# type-1_4_button_v4.net
KiCad netlist of a schematic drawn in EAGLE
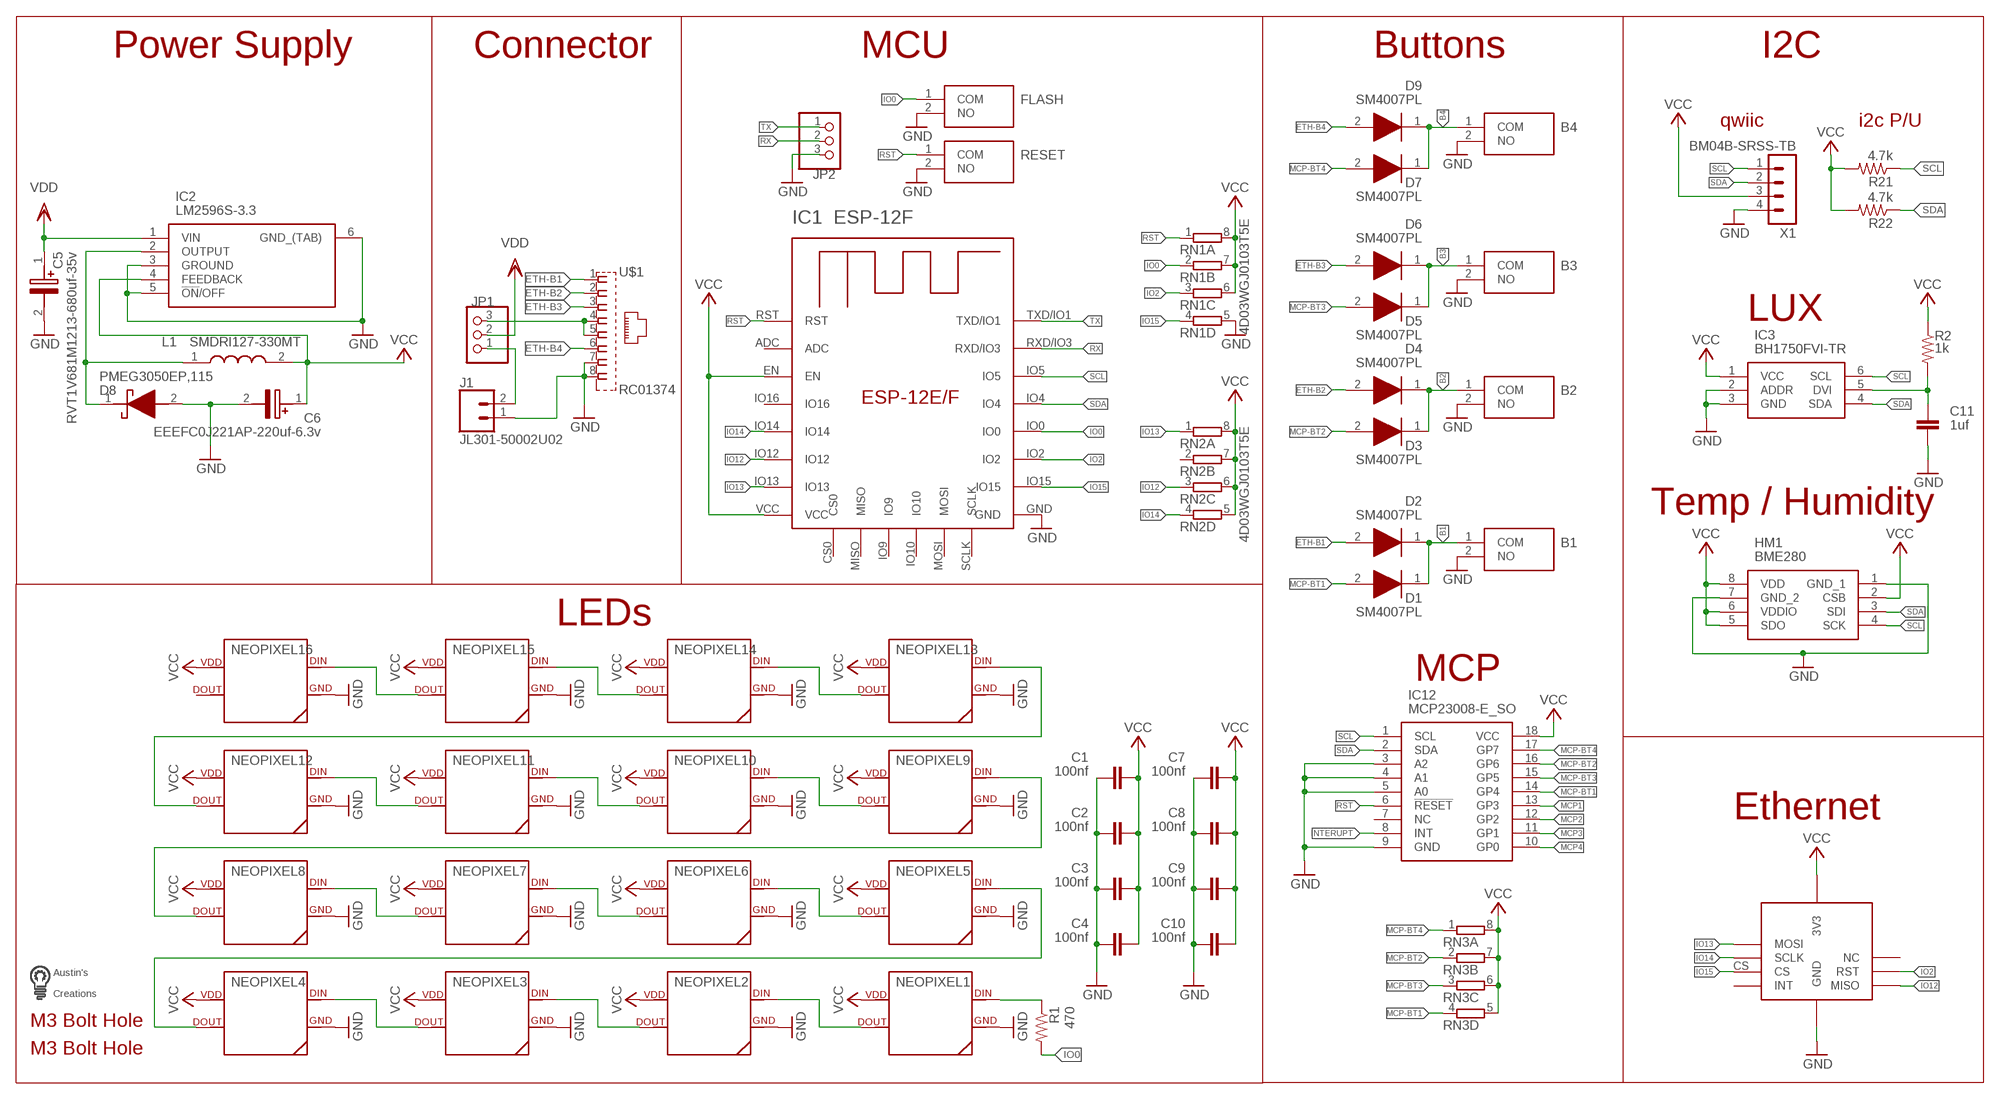
[diagram p0: schematic, sheet 1]

(export (version "E")
  (design (tool "Eeschema 10.0.6"))
  (components
    (comp (ref "B1")
      (value "PTS636_SM25F_SMTR_LFS")
      (footprint "eagle-import:PTS636SM25FSMTRLFS")
      (fields
        (field (name "ARROW_PART_NUMBER") "PTS636 SM25F SMTR LFS")
        (field (name "MOUSER_PART_NUMBER") "611-PTS636SM25FSMTRL")
      )
      (libsource (lib "eagle-import") (part "PTS636_SM25F_SMTR_LFS"))
    )
    (comp (ref "B2")
      (value "PTS636_SM25F_SMTR_LFS")
      (footprint "eagle-import:PTS636SM25FSMTRLFS")
      (fields
        (field (name "ARROW_PART_NUMBER") "PTS636 SM25F SMTR LFS")
        (field (name "MOUSER_PART_NUMBER") "611-PTS636SM25FSMTRL")
      )
      (libsource (lib "eagle-import") (part "PTS636_SM25F_SMTR_LFS"))
    )
    (comp (ref "B3")
      (value "PTS636_SM25F_SMTR_LFS")
      (footprint "eagle-import:PTS636SM25FSMTRLFS")
      (fields
        (field (name "ARROW_PART_NUMBER") "PTS636 SM25F SMTR LFS")
        (field (name "MOUSER_PART_NUMBER") "611-PTS636SM25FSMTRL")
      )
      (libsource (lib "eagle-import") (part "PTS636_SM25F_SMTR_LFS"))
    )
    (comp (ref "B4")
      (value "PTS636_SM25F_SMTR_LFS")
      (footprint "eagle-import:PTS636SM25FSMTRLFS")
      (fields
        (field (name "ARROW_PART_NUMBER") "PTS636 SM25F SMTR LFS")
        (field (name "MOUSER_PART_NUMBER") "611-PTS636SM25FSMTRL")
      )
      (libsource (lib "eagle-import") (part "PTS636_SM25F_SMTR_LFS"))
    )
    (comp (ref "C1")
      (value "100nf")
      (footprint "eagle-import:C0603")
      (libsource (lib "eagle-import") (part "C-EUC0603"))
    )
    (comp (ref "C2")
      (value "100nf")
      (footprint "eagle-import:C0603")
      (libsource (lib "eagle-import") (part "C-EUC0603"))
    )
    (comp (ref "C3")
      (value "100nf")
      (footprint "eagle-import:C0603")
      (libsource (lib "eagle-import") (part "C-EUC0603"))
    )
    (comp (ref "C4")
      (value "100nf")
      (footprint "eagle-import:C0603")
      (libsource (lib "eagle-import") (part "C-EUC0603"))
    )
    (comp (ref "C5")
      (value "RVT1V681M1213-680uf-35v")
      (footprint "eagle-import:CAPAE1350X1400N")
      (fields
        (field (name "MANUFACTURER_PART_NUMBER") "EEE-HD1V681AQ")
        (field (name "MOUSER_PART_NUMBER") "667-EEE-HD1V681AQ")
      )
      (libsource (lib "eagle-import") (part "EEE-HD1V681AQ"))
    )
    (comp (ref "C6")
      (value "EEEFC0J221AP-220uf-6.3v")
      (footprint "eagle-import:CAPAE830X650N")
      (fields (field (name "MANUFACTURER_PART_NUMBER") "EEEFC0J221AP"))
      (libsource (lib "eagle-import") (part "EEEFC0J221AP"))
    )
    (comp (ref "C7")
      (value "100nf")
      (footprint "eagle-import:C0603")
      (libsource (lib "eagle-import") (part "C-EUC0603"))
    )
    (comp (ref "C8")
      (value "100nf")
      (footprint "eagle-import:C0603")
      (libsource (lib "eagle-import") (part "C-EUC0603"))
    )
    (comp (ref "C9")
      (value "100nf")
      (footprint "eagle-import:C0603")
      (libsource (lib "eagle-import") (part "C-EUC0603"))
    )
    (comp (ref "C10")
      (value "100nf")
      (footprint "eagle-import:C0603")
      (libsource (lib "eagle-import") (part "C-EUC0603"))
    )
    (comp (ref "C11")
      (value "1uf")
      (footprint "eagle-import:C0603")
      (libsource (lib "eagle-import") (part "C-EUC0603"))
    )
    (comp (ref "D1")
      (value "SM4007PL")
      (footprint "eagle-import:SODFL3718X125N")
      (libsource (lib "eagle-import") (part "SM4007PL"))
    )
    (comp (ref "D2")
      (value "SM4007PL")
      (footprint "eagle-import:SODFL3718X125N")
      (libsource (lib "eagle-import") (part "SM4007PL"))
    )
    (comp (ref "D3")
      (value "SM4007PL")
      (footprint "eagle-import:SODFL3718X125N")
      (libsource (lib "eagle-import") (part "SM4007PL"))
    )
    (comp (ref "D4")
      (value "SM4007PL")
      (footprint "eagle-import:SODFL3718X125N")
      (libsource (lib "eagle-import") (part "SM4007PL"))
    )
    (comp (ref "D5")
      (value "SM4007PL")
      (footprint "eagle-import:SODFL3718X125N")
      (libsource (lib "eagle-import") (part "SM4007PL"))
    )
    (comp (ref "D6")
      (value "SM4007PL")
      (footprint "eagle-import:SODFL3718X125N")
      (libsource (lib "eagle-import") (part "SM4007PL"))
    )
    (comp (ref "D7")
      (value "SM4007PL")
      (footprint "eagle-import:SODFL3718X125N")
      (libsource (lib "eagle-import") (part "SM4007PL"))
    )
    (comp (ref "D8")
      (value "PMEG3050EP,115")
      (footprint "eagle-import:PMEG3050EP115")
      (fields (field (name "MOUSER_PART_NUMBER") "771-PMEG3050EP115"))
      (libsource (lib "eagle-import") (part "PMEG3050EP,115"))
    )
    (comp (ref "D9")
      (value "SM4007PL")
      (footprint "eagle-import:SODFL3718X125N")
      (libsource (lib "eagle-import") (part "SM4007PL"))
    )
    (comp (ref "FLASH")
      (value "PTS636_SM25F_SMTR_LFS")
      (footprint "eagle-import:PTS636SM25FSMTRLFS")
      (fields
        (field (name "ARROW_PART_NUMBER") "PTS636 SM25F SMTR LFS")
        (field (name "MOUSER_PART_NUMBER") "611-PTS636SM25FSMTRL")
      )
      (libsource (lib "eagle-import") (part "PTS636_SM25F_SMTR_LFS"))
    )
    (comp (ref "HM1")
      (value "BME280")
      (footprint "eagle-import:BME280")
      (fields (field (name "MOUSER_PART_NUMBER") "262-BME280"))
      (libsource (lib "eagle-import") (part "BME280"))
    )
    (comp (ref "IC1")
      (value "ESP-12F")
      (footprint "eagle-import:ESP-12E")
      (libsource (lib "eagle-import") (part "ESP-12E/F"))
    )
    (comp (ref "IC2")
      (value "LM2596S-3.3")
      (footprint "eagle-import:TO170P1435X465-6N")
      (fields
        (field (name "MANUFACTURER_PART_NUMBER") "LM2596S-3.3/NOPB")
        (field (name "MOUSER_PART_NUMBER") "926-LM2596S-3.3/NOPB")
      )
      (libsource (lib "eagle-import") (part "LM2596S-3.3_NOPB"))
    )
    (comp (ref "IC3")
      (value "BH1750FVI-TR")
      (footprint "eagle-import:WSOF6")
      (fields (field (name "MOUSER_PART_NUMBER") "755-BH1750FVI-TR"))
      (libsource (lib "eagle-import") (part "BH1750FVI-TR"))
    )
    (comp (ref "IC12")
      (value "MCP23008-E_SO")
      (footprint "eagle-import:SOIC127P1030X265-18N")
      (fields
        (field (name "ARROW_PART_NUMBER") "MCP23008-E/SO")
        (field (name "MOUSER_PART_NUMBER") "579-MCP23008-E/SO")
      )
      (libsource (lib "eagle-import") (part "MCP23008-E_SO"))
    )
    (comp (ref "J1")
      (value "JL301-50002U02")
      (footprint "eagle-import:SCREWTERMINAL-5MM-2")
      (libsource (lib "eagle-import") (part "2PINBLOCK"))
    )
    (comp (ref "JP1")
      (value "PINHD-1X3")
      (footprint "eagle-import:1X03")
      (libsource (lib "eagle-import") (part "PINHD-1X3"))
    )
    (comp (ref "JP2")
      (value "PINHD-1X3")
      (footprint "eagle-import:1X03")
      (libsource (lib "eagle-import") (part "PINHD-1X3"))
    )
    (comp (ref "L1")
      (value "SMDRI127-330MT")
      (footprint "eagle-import:INDPM120120X800N")
      (fields
        (field (name "MANUFACTURER_PART_NUMBER") "CDRH127/LDNP-330MC")
        (field (name "MOUSER_PART_NUMBER") "851-CDRH127LDNP330MC")
      )
      (libsource (lib "eagle-import") (part "CDRH127_LDNP-330MC"))
    )
    (comp (ref "NEOPIXEL1")
      (value "SK6812NEOPIXEL5050")
      (footprint "eagle-import:SK6812")
      (libsource (lib "eagle-import") (part "SK68125050NEOPIXEL"))
    )
    (comp (ref "NEOPIXEL2")
      (value "SK6812NEOPIXEL5050")
      (footprint "eagle-import:SK6812")
      (libsource (lib "eagle-import") (part "SK68125050NEOPIXEL"))
    )
    (comp (ref "NEOPIXEL3")
      (value "SK6812NEOPIXEL5050")
      (footprint "eagle-import:SK6812")
      (libsource (lib "eagle-import") (part "SK68125050NEOPIXEL"))
    )
    (comp (ref "NEOPIXEL4")
      (value "SK6812NEOPIXEL5050")
      (footprint "eagle-import:SK6812")
      (libsource (lib "eagle-import") (part "SK68125050NEOPIXEL"))
    )
    (comp (ref "NEOPIXEL5")
      (value "SK6812NEOPIXEL5050")
      (footprint "eagle-import:SK6812")
      (libsource (lib "eagle-import") (part "SK68125050NEOPIXEL"))
    )
    (comp (ref "NEOPIXEL6")
      (value "SK6812NEOPIXEL5050")
      (footprint "eagle-import:SK6812")
      (libsource (lib "eagle-import") (part "SK68125050NEOPIXEL"))
    )
    (comp (ref "NEOPIXEL7")
      (value "SK6812NEOPIXEL5050")
      (footprint "eagle-import:SK6812")
      (libsource (lib "eagle-import") (part "SK68125050NEOPIXEL"))
    )
    (comp (ref "NEOPIXEL8")
      (value "SK6812NEOPIXEL5050")
      (footprint "eagle-import:SK6812")
      (libsource (lib "eagle-import") (part "SK68125050NEOPIXEL"))
    )
    (comp (ref "NEOPIXEL9")
      (value "SK6812NEOPIXEL5050")
      (footprint "eagle-import:SK6812")
      (libsource (lib "eagle-import") (part "SK68125050NEOPIXEL"))
    )
    (comp (ref "NEOPIXEL10")
      (value "SK6812NEOPIXEL5050")
      (footprint "eagle-import:SK6812")
      (libsource (lib "eagle-import") (part "SK68125050NEOPIXEL"))
    )
    (comp (ref "NEOPIXEL11")
      (value "SK6812NEOPIXEL5050")
      (footprint "eagle-import:SK6812")
      (libsource (lib "eagle-import") (part "SK68125050NEOPIXEL"))
    )
    (comp (ref "NEOPIXEL12")
      (value "SK6812NEOPIXEL5050")
      (footprint "eagle-import:SK6812")
      (libsource (lib "eagle-import") (part "SK68125050NEOPIXEL"))
    )
    (comp (ref "NEOPIXEL13")
      (value "SK6812NEOPIXEL5050")
      (footprint "eagle-import:SK6812")
      (libsource (lib "eagle-import") (part "SK68125050NEOPIXEL"))
    )
    (comp (ref "NEOPIXEL14")
      (value "SK6812NEOPIXEL5050")
      (footprint "eagle-import:SK6812")
      (libsource (lib "eagle-import") (part "SK68125050NEOPIXEL"))
    )
    (comp (ref "NEOPIXEL15")
      (value "SK6812NEOPIXEL5050")
      (footprint "eagle-import:SK6812")
      (libsource (lib "eagle-import") (part "SK68125050NEOPIXEL"))
    )
    (comp (ref "NEOPIXEL16")
      (value "SK6812NEOPIXEL5050")
      (footprint "eagle-import:SK6812")
      (libsource (lib "eagle-import") (part "SK68125050NEOPIXEL"))
    )
    (comp (ref "R1")
      (value "470")
      (footprint "eagle-import:R0603")
      (libsource (lib "eagle-import") (part "resistor_348_R-US_R0603"))
    )
    (comp (ref "R2")
      (value "1k")
      (footprint "eagle-import:R0603")
      (libsource (lib "eagle-import") (part "resistor_348_R-US_R0603"))
    )
    (comp (ref "R21")
      (value "4.7k")
      (footprint "eagle-import:R0603")
      (libsource (lib "eagle-import") (part "R-US_R0603"))
    )
    (comp (ref "R22")
      (value "4.7k")
      (footprint "eagle-import:R0603")
      (libsource (lib "eagle-import") (part "R-US_R0603"))
    )
    (comp (ref "RESET")
      (value "PTS636_SM25F_SMTR_LFS")
      (footprint "eagle-import:PTS636SM25FSMTRLFS")
      (fields
        (field (name "ARROW_PART_NUMBER") "PTS636 SM25F SMTR LFS")
        (field (name "MOUSER_PART_NUMBER") "611-PTS636SM25FSMTRL")
      )
      (libsource (lib "eagle-import") (part "PTS636_SM25F_SMTR_LFS"))
    )
    (comp (ref "RN1")
      (value "4R-N0603-ARC")
      (footprint "eagle-import:0603-ARC")
      (libsource (lib "eagle-import") (part "4R-N0603-ARC"))
    )
    (comp (ref "RN2")
      (value "4R-N0603-ARC")
      (footprint "eagle-import:0603-ARC")
      (libsource (lib "eagle-import") (part "4R-N0603-ARC"))
    )
    (comp (ref "RN3")
      (value "4R-N0603-ARC")
      (footprint "eagle-import:0603-ARC")
      (libsource (lib "eagle-import") (part "4R-N0603-ARC"))
    )
    (comp (ref "U$1")
      (value "RC01374")
      (footprint "eagle-import:RC01374")
      (libsource (lib "eagle-import") (part "RC01374"))
    )
    (comp (ref "U$3")
      (value "W5500MODULE")
      (footprint "eagle-import:W5500MODULE")
      (libsource (lib "eagle-import") (part "W5500MODULE"))
    )
    (comp (ref "U$4")
      (value "M3BOLTHOLE")
      (footprint "eagle-import:M3BOLTHOLE")
      (libsource (lib "eagle-import") (part "M3BOLTHOLE"))
    )
    (comp (ref "U$5")
      (value "M3BOLTHOLE")
      (footprint "eagle-import:M3BOLTHOLE")
      (libsource (lib "eagle-import") (part "M3BOLTHOLE"))
    )
    (comp (ref "U$6")
      (value "LOGOMED")
      (footprint "eagle-import:LOGOMED")
      (libsource (lib "eagle-import") (part "LOGOMED"))
    )
    (comp (ref "X1")
      (value "BM04B-SRSS-TB")
      (footprint "eagle-import:BM04B-SRSS-TB")
      (libsource (lib "eagle-import") (part "BM04B-SRSS-TB"))
    )
  )
  (nets
    (net (code "1") (name "B1") (class "Default")
      (node (ref "B1") (pin "1") (pinfunction "COM_1") (pintype "bidirectional"))
      (node (ref "D1") (pin "1") (pinfunction "K_1") (pintype "bidirectional"))
      (node (ref "D2") (pin "1") (pinfunction "K_1") (pintype "bidirectional"))
    )
    (net (code "2") (name "B2") (class "Default")
      (node (ref "B2") (pin "1") (pinfunction "COM_1") (pintype "bidirectional"))
      (node (ref "D3") (pin "1") (pinfunction "K_1") (pintype "bidirectional"))
      (node (ref "D4") (pin "1") (pinfunction "K_1") (pintype "bidirectional"))
    )
    (net (code "3") (name "B3") (class "Default")
      (node (ref "B3") (pin "1") (pinfunction "COM_1") (pintype "bidirectional"))
      (node (ref "D5") (pin "1") (pinfunction "K_1") (pintype "bidirectional"))
      (node (ref "D6") (pin "1") (pinfunction "K_1") (pintype "bidirectional"))
    )
    (net (code "4") (name "B4") (class "Default")
      (node (ref "B4") (pin "1") (pinfunction "COM_1") (pintype "bidirectional"))
      (node (ref "D7") (pin "1") (pinfunction "K_1") (pintype "bidirectional"))
      (node (ref "D9") (pin "1") (pinfunction "K_1") (pintype "bidirectional"))
    )
    (net (code "5") (name "ETH-B1") (class "Default")
      (node (ref "D2") (pin "2") (pinfunction "A_2") (pintype "bidirectional"))
      (node (ref "U$1") (pin "1") (pinfunction "1_1") (pintype "passive"))
    )
    (net (code "6") (name "ETH-B2") (class "Default")
      (node (ref "D4") (pin "2") (pinfunction "A_2") (pintype "bidirectional"))
      (node (ref "U$1") (pin "2") (pinfunction "2_2") (pintype "passive"))
    )
    (net (code "7") (name "ETH-B3") (class "Default")
      (node (ref "D6") (pin "2") (pinfunction "A_2") (pintype "bidirectional"))
      (node (ref "U$1") (pin "3") (pinfunction "3_3") (pintype "passive"))
    )
    (net (code "8") (name "ETH-B4") (class "Default")
      (node (ref "D9") (pin "2") (pinfunction "A_2") (pintype "bidirectional"))
      (node (ref "U$1") (pin "6") (pinfunction "6_6") (pintype "passive"))
    )
    (net (code "9") (name "GND") (class "Default")
      (node (ref "B1") (pin "2") (pinfunction "NO_2") (pintype "bidirectional"))
      (node (ref "B2") (pin "2") (pinfunction "NO_2") (pintype "bidirectional"))
      (node (ref "B3") (pin "2") (pinfunction "NO_2") (pintype "bidirectional"))
      (node (ref "B4") (pin "2") (pinfunction "NO_2") (pintype "bidirectional"))
      (node (ref "C1") (pin "1") (pinfunction "1_1") (pintype "passive"))
      (node (ref "C10") (pin "1") (pinfunction "1_1") (pintype "passive"))
      (node (ref "C11") (pin "2") (pinfunction "2_2") (pintype "passive"))
      (node (ref "C2") (pin "1") (pinfunction "1_1") (pintype "passive"))
      (node (ref "C3") (pin "1") (pinfunction "1_1") (pintype "passive"))
      (node (ref "C4") (pin "1") (pinfunction "1_1") (pintype "passive"))
      (node (ref "C5") (pin "2") (pinfunction "-_2") (pintype "bidirectional"))
      (node (ref "C6") (pin "2") (pinfunction "-_2") (pintype "bidirectional"))
      (node (ref "C7") (pin "1") (pinfunction "1_1") (pintype "passive"))
      (node (ref "C8") (pin "1") (pinfunction "1_1") (pintype "passive"))
      (node (ref "C9") (pin "1") (pinfunction "1_1") (pintype "passive"))
      (node (ref "D8") (pin "2") (pinfunction "A_2") (pintype "bidirectional"))
      (node (ref "FLASH") (pin "2") (pinfunction "NO_2") (pintype "bidirectional"))
      (node (ref "HM1") (pin "1") (pinfunction "GND_1_1") (pintype "power_in"))
      (node (ref "HM1") (pin "7") (pinfunction "GND_2_7") (pintype "power_in"))
      (node (ref "IC1") (pin "GND") (pinfunction "GND_GND") (pintype "power_in"))
      (node (ref "IC12") (pin "3") (pinfunction "A2_3") (pintype "bidirectional"))
      (node (ref "IC12") (pin "4") (pinfunction "A1_4") (pintype "bidirectional"))
      (node (ref "IC12") (pin "5") (pinfunction "A0_5") (pintype "bidirectional"))
      (node (ref "IC12") (pin "9") (pinfunction "GND_9") (pintype "bidirectional"))
      (node (ref "IC2") (pin "3") (pinfunction "GROUND_3") (pintype "bidirectional"))
      (node (ref "IC2") (pin "5") (pinfunction "~{ON}/OFF_5") (pintype "bidirectional"))
      (node (ref "IC2") (pin "6") (pinfunction "GND_(TAB)_6") (pintype "power_in"))
      (node (ref "IC3") (pin "2") (pinfunction "ADDR_2") (pintype "bidirectional"))
      (node (ref "IC3") (pin "3") (pinfunction "GND_3") (pintype "bidirectional"))
      (node (ref "J1") (pin "1") (pinfunction "1_1") (pintype "passive"))
      (node (ref "JP2") (pin "3") (pinfunction "3_3") (pintype "passive"))
      (node (ref "NEOPIXEL1") (pin "3") (pinfunction "GND_3") (pintype "bidirectional"))
      (node (ref "NEOPIXEL10") (pin "3") (pinfunction "GND_3") (pintype "bidirectional"))
      (node (ref "NEOPIXEL11") (pin "3") (pinfunction "GND_3") (pintype "bidirectional"))
      (node (ref "NEOPIXEL12") (pin "3") (pinfunction "GND_3") (pintype "bidirectional"))
      (node (ref "NEOPIXEL13") (pin "3") (pinfunction "GND_3") (pintype "bidirectional"))
      (node (ref "NEOPIXEL14") (pin "3") (pinfunction "GND_3") (pintype "bidirectional"))
      (node (ref "NEOPIXEL15") (pin "3") (pinfunction "GND_3") (pintype "bidirectional"))
      (node (ref "NEOPIXEL16") (pin "3") (pinfunction "GND_3") (pintype "bidirectional"))
      (node (ref "NEOPIXEL2") (pin "3") (pinfunction "GND_3") (pintype "bidirectional"))
      (node (ref "NEOPIXEL3") (pin "3") (pinfunction "GND_3") (pintype "bidirectional"))
      (node (ref "NEOPIXEL4") (pin "3") (pinfunction "GND_3") (pintype "bidirectional"))
      (node (ref "NEOPIXEL5") (pin "3") (pinfunction "GND_3") (pintype "bidirectional"))
      (node (ref "NEOPIXEL6") (pin "3") (pinfunction "GND_3") (pintype "bidirectional"))
      (node (ref "NEOPIXEL7") (pin "3") (pinfunction "GND_3") (pintype "bidirectional"))
      (node (ref "NEOPIXEL8") (pin "3") (pinfunction "GND_3") (pintype "bidirectional"))
      (node (ref "NEOPIXEL9") (pin "3") (pinfunction "GND_3") (pintype "bidirectional"))
      (node (ref "RESET") (pin "2") (pinfunction "NO_2") (pintype "bidirectional"))
      (node (ref "RN1") (pin "5") (pinfunction "2_5") (pintype "passive"))
      (node (ref "U$1") (pin "7") (pinfunction "7_7") (pintype "passive"))
      (node (ref "U$1") (pin "8") (pinfunction "8_8") (pintype "passive"))
      (node (ref "U$3") (pin "GND1") (pinfunction "GND_GND1") (pintype "bidirectional"))
      (node (ref "U$3") (pin "GND2") (pinfunction "GND_GND2") (pintype "bidirectional"))
      (node (ref "U$3") (pin "GND3") (pinfunction "GND_GND3") (pintype "bidirectional"))
      (node (ref "X1") (pin "4") (pinfunction "4_4") (pintype "passive"))
    )
    (net (code "10") (name "INTERUPT") (class "Default")
      (node (ref "IC12") (pin "8") (pinfunction "INT_8") (pintype "bidirectional"))
    )
    (net (code "11") (name "IO0") (class "Default")
      (node (ref "FLASH") (pin "1") (pinfunction "COM_1") (pintype "bidirectional"))
      (node (ref "IC1") (pin "IO0") (pinfunction "IO0_IO0") (pintype "bidirectional"))
      (node (ref "R1") (pin "2") (pinfunction "2_2") (pintype "passive"))
      (node (ref "RN1") (pin "2") (pinfunction "1_2") (pintype "passive"))
    )
    (net (code "12") (name "IO2") (class "Default")
      (node (ref "IC1") (pin "IO2") (pinfunction "IO2_IO2") (pintype "bidirectional"))
      (node (ref "RN1") (pin "3") (pinfunction "1_3") (pintype "passive"))
      (node (ref "U$3") (pin "RST") (pinfunction "RST_RST") (pintype "bidirectional"))
    )
    (net (code "13") (name "IO12") (class "Default")
      (node (ref "IC1") (pin "IO12") (pinfunction "IO12_IO12") (pintype "bidirectional"))
      (node (ref "RN2") (pin "3") (pinfunction "1_3") (pintype "passive"))
      (node (ref "U$3") (pin "MISO") (pinfunction "MISO_MISO") (pintype "bidirectional"))
    )
    (net (code "14") (name "IO13") (class "Default")
      (node (ref "IC1") (pin "IO13") (pinfunction "IO13_IO13") (pintype "bidirectional"))
      (node (ref "RN2") (pin "1") (pinfunction "1_1") (pintype "passive"))
      (node (ref "U$3") (pin "MOSI") (pinfunction "MOSI_MOSI") (pintype "bidirectional"))
    )
    (net (code "15") (name "IO14") (class "Default")
      (node (ref "IC1") (pin "IO14") (pinfunction "IO14_IO14") (pintype "bidirectional"))
      (node (ref "RN2") (pin "4") (pinfunction "1_4") (pintype "passive"))
      (node (ref "U$3") (pin "SCLK") (pinfunction "SCLK_SCLK") (pintype "bidirectional"))
    )
    (net (code "16") (name "IO15") (class "Default")
      (node (ref "IC1") (pin "IO15") (pinfunction "IO15_IO15") (pintype "bidirectional"))
      (node (ref "RN1") (pin "4") (pinfunction "1_4") (pintype "passive"))
      (node (ref "U$3") (pin "CS") (pinfunction "CS_CS") (pintype "bidirectional"))
    )
    (net (code "17") (name "MCP-BT1") (class "Default")
      (node (ref "D1") (pin "2") (pinfunction "A_2") (pintype "bidirectional"))
      (node (ref "IC12") (pin "14") (pinfunction "GP4_14") (pintype "bidirectional"))
      (node (ref "RN3") (pin "4") (pinfunction "1_4") (pintype "passive"))
    )
    (net (code "18") (name "MCP-BT2") (class "Default")
      (node (ref "D3") (pin "2") (pinfunction "A_2") (pintype "bidirectional"))
      (node (ref "IC12") (pin "16") (pinfunction "GP6_16") (pintype "bidirectional"))
      (node (ref "RN3") (pin "2") (pinfunction "1_2") (pintype "passive"))
    )
    (net (code "19") (name "MCP-BT3") (class "Default")
      (node (ref "D5") (pin "2") (pinfunction "A_2") (pintype "bidirectional"))
      (node (ref "IC12") (pin "15") (pinfunction "GP5_15") (pintype "bidirectional"))
      (node (ref "RN3") (pin "3") (pinfunction "1_3") (pintype "passive"))
    )
    (net (code "20") (name "MCP-BT4") (class "Default")
      (node (ref "D7") (pin "2") (pinfunction "A_2") (pintype "bidirectional"))
      (node (ref "IC12") (pin "17") (pinfunction "GP7_17") (pintype "bidirectional"))
      (node (ref "RN3") (pin "1") (pinfunction "1_1") (pintype "passive"))
    )
    (net (code "21") (name "MCP1") (class "Default")
      (node (ref "IC12") (pin "13") (pinfunction "GP3_13") (pintype "bidirectional"))
    )
    (net (code "22") (name "MCP2") (class "Default")
      (node (ref "IC12") (pin "12") (pinfunction "GP2_12") (pintype "bidirectional"))
    )
    (net (code "23") (name "MCP3") (class "Default")
      (node (ref "IC12") (pin "11") (pinfunction "GP1_11") (pintype "bidirectional"))
    )
    (net (code "24") (name "MCP4") (class "Default")
      (node (ref "IC12") (pin "10") (pinfunction "GP0_10") (pintype "bidirectional"))
    )
    (net (code "25") (name "Net-(D8-K)") (class "Default")
      (node (ref "D8") (pin "1") (pinfunction "K_1") (pintype "bidirectional"))
      (node (ref "IC2") (pin "2") (pinfunction "OUTPUT_2") (pintype "output"))
      (node (ref "L1") (pin "1") (pinfunction "1_1") (pintype "bidirectional"))
    )
    (net (code "26") (name "Net-(IC3-DVI)") (class "Default")
      (node (ref "C11") (pin "1") (pinfunction "1_1") (pintype "passive"))
      (node (ref "IC3") (pin "5") (pinfunction "DVI_5") (pintype "bidirectional"))
      (node (ref "R2") (pin "2") (pinfunction "2_2") (pintype "passive"))
    )
    (net (code "27") (name "Net-(J1-Pad2)") (class "Default")
      (node (ref "J1") (pin "2") (pinfunction "2_2") (pintype "passive"))
      (node (ref "JP1") (pin "1") (pinfunction "1_1") (pintype "passive"))
    )
    (net (code "28") (name "Net-(JP1-Pad3)") (class "Default")
      (node (ref "JP1") (pin "3") (pinfunction "3_3") (pintype "passive"))
      (node (ref "U$1") (pin "4") (pinfunction "4_4") (pintype "passive"))
      (node (ref "U$1") (pin "5") (pinfunction "5_5") (pintype "passive"))
    )
    (net (code "29") (name "Net-(NEOPIXEL1-DIN)") (class "Default")
      (node (ref "NEOPIXEL1") (pin "4") (pinfunction "DIN_4") (pintype "bidirectional"))
      (node (ref "R1") (pin "1") (pinfunction "1_1") (pintype "passive"))
    )
    (net (code "30") (name "Net-(NEOPIXEL1-DOUT)") (class "Default")
      (node (ref "NEOPIXEL1") (pin "2") (pinfunction "DOUT_2") (pintype "bidirectional"))
      (node (ref "NEOPIXEL2") (pin "4") (pinfunction "DIN_4") (pintype "bidirectional"))
    )
    (net (code "31") (name "Net-(NEOPIXEL2-DOUT)") (class "Default")
      (node (ref "NEOPIXEL2") (pin "2") (pinfunction "DOUT_2") (pintype "bidirectional"))
      (node (ref "NEOPIXEL3") (pin "4") (pinfunction "DIN_4") (pintype "bidirectional"))
    )
    (net (code "32") (name "Net-(NEOPIXEL3-DOUT)") (class "Default")
      (node (ref "NEOPIXEL3") (pin "2") (pinfunction "DOUT_2") (pintype "bidirectional"))
      (node (ref "NEOPIXEL4") (pin "4") (pinfunction "DIN_4") (pintype "bidirectional"))
    )
    (net (code "33") (name "Net-(NEOPIXEL4-DOUT)") (class "Default")
      (node (ref "NEOPIXEL4") (pin "2") (pinfunction "DOUT_2") (pintype "bidirectional"))
      (node (ref "NEOPIXEL5") (pin "4") (pinfunction "DIN_4") (pintype "bidirectional"))
    )
    (net (code "34") (name "Net-(NEOPIXEL5-DOUT)") (class "Default")
      (node (ref "NEOPIXEL5") (pin "2") (pinfunction "DOUT_2") (pintype "bidirectional"))
      (node (ref "NEOPIXEL6") (pin "4") (pinfunction "DIN_4") (pintype "bidirectional"))
    )
    (net (code "35") (name "Net-(NEOPIXEL6-DOUT)") (class "Default")
      (node (ref "NEOPIXEL6") (pin "2") (pinfunction "DOUT_2") (pintype "bidirectional"))
      (node (ref "NEOPIXEL7") (pin "4") (pinfunction "DIN_4") (pintype "bidirectional"))
    )
    (net (code "36") (name "Net-(NEOPIXEL7-DOUT)") (class "Default")
      (node (ref "NEOPIXEL7") (pin "2") (pinfunction "DOUT_2") (pintype "bidirectional"))
      (node (ref "NEOPIXEL8") (pin "4") (pinfunction "DIN_4") (pintype "bidirectional"))
    )
    (net (code "37") (name "Net-(NEOPIXEL8-DOUT)") (class "Default")
      (node (ref "NEOPIXEL8") (pin "2") (pinfunction "DOUT_2") (pintype "bidirectional"))
      (node (ref "NEOPIXEL9") (pin "4") (pinfunction "DIN_4") (pintype "bidirectional"))
    )
    (net (code "38") (name "Net-(NEOPIXEL10-DIN)") (class "Default")
      (node (ref "NEOPIXEL10") (pin "4") (pinfunction "DIN_4") (pintype "bidirectional"))
      (node (ref "NEOPIXEL9") (pin "2") (pinfunction "DOUT_2") (pintype "bidirectional"))
    )
    (net (code "39") (name "Net-(NEOPIXEL10-DOUT)") (class "Default")
      (node (ref "NEOPIXEL10") (pin "2") (pinfunction "DOUT_2") (pintype "bidirectional"))
      (node (ref "NEOPIXEL11") (pin "4") (pinfunction "DIN_4") (pintype "bidirectional"))
    )
    (net (code "40") (name "Net-(NEOPIXEL11-DOUT)") (class "Default")
      (node (ref "NEOPIXEL11") (pin "2") (pinfunction "DOUT_2") (pintype "bidirectional"))
      (node (ref "NEOPIXEL12") (pin "4") (pinfunction "DIN_4") (pintype "bidirectional"))
    )
    (net (code "41") (name "Net-(NEOPIXEL12-DOUT)") (class "Default")
      (node (ref "NEOPIXEL12") (pin "2") (pinfunction "DOUT_2") (pintype "bidirectional"))
      (node (ref "NEOPIXEL13") (pin "4") (pinfunction "DIN_4") (pintype "bidirectional"))
    )
    (net (code "42") (name "Net-(NEOPIXEL13-DOUT)") (class "Default")
      (node (ref "NEOPIXEL13") (pin "2") (pinfunction "DOUT_2") (pintype "bidirectional"))
      (node (ref "NEOPIXEL14") (pin "4") (pinfunction "DIN_4") (pintype "bidirectional"))
    )
    (net (code "43") (name "Net-(NEOPIXEL14-DOUT)") (class "Default")
      (node (ref "NEOPIXEL14") (pin "2") (pinfunction "DOUT_2") (pintype "bidirectional"))
      (node (ref "NEOPIXEL15") (pin "4") (pinfunction "DIN_4") (pintype "bidirectional"))
    )
    (net (code "44") (name "Net-(NEOPIXEL15-DOUT)") (class "Default")
      (node (ref "NEOPIXEL15") (pin "2") (pinfunction "DOUT_2") (pintype "bidirectional"))
      (node (ref "NEOPIXEL16") (pin "4") (pinfunction "DIN_4") (pintype "bidirectional"))
    )
    (net (code "45") (name "RST") (class "Default")
      (node (ref "IC1") (pin "RST") (pinfunction "RST_RST") (pintype "input"))
      (node (ref "IC12") (pin "6") (pinfunction "~{RESET}_6") (pintype "bidirectional"))
      (node (ref "RESET") (pin "1") (pinfunction "COM_1") (pintype "bidirectional"))
      (node (ref "RN1") (pin "1") (pinfunction "1_1") (pintype "passive"))
    )
    (net (code "46") (name "RX") (class "Default")
      (node (ref "IC1") (pin "RXD/IO3") (pinfunction "RXD/IO3_RXD/IO3") (pintype "bidirectional"))
      (node (ref "JP2") (pin "2") (pinfunction "2_2") (pintype "passive"))
    )
    (net (code "47") (name "SCL") (class "Default")
      (node (ref "HM1") (pin "4") (pinfunction "SCK_4") (pintype "bidirectional"))
      (node (ref "IC1") (pin "IO5") (pinfunction "IO5_IO5") (pintype "bidirectional"))
      (node (ref "IC12") (pin "1") (pinfunction "SCL_1") (pintype "bidirectional"))
      (node (ref "IC3") (pin "6") (pinfunction "SCL_6") (pintype "bidirectional"))
      (node (ref "R21") (pin "1") (pinfunction "1_1") (pintype "passive"))
      (node (ref "X1") (pin "1") (pinfunction "1_1") (pintype "passive"))
    )
    (net (code "48") (name "SDA") (class "Default")
      (node (ref "HM1") (pin "3") (pinfunction "SDI_3") (pintype "bidirectional"))
      (node (ref "IC1") (pin "IO4") (pinfunction "IO4_IO4") (pintype "bidirectional"))
      (node (ref "IC12") (pin "2") (pinfunction "SDA_2") (pintype "bidirectional"))
      (node (ref "IC3") (pin "4") (pinfunction "SDA_4") (pintype "bidirectional"))
      (node (ref "R22") (pin "1") (pinfunction "1_1") (pintype "passive"))
      (node (ref "X1") (pin "2") (pinfunction "2_2") (pintype "passive"))
    )
    (net (code "49") (name "TX") (class "Default")
      (node (ref "IC1") (pin "TXD/IO1") (pinfunction "TXD/IO1_TXD/IO1") (pintype "bidirectional"))
      (node (ref "JP2") (pin "1") (pinfunction "1_1") (pintype "passive"))
    )
    (net (code "50") (name "VCC") (class "Default")
      (node (ref "C1") (pin "2") (pinfunction "2_2") (pintype "passive"))
      (node (ref "C10") (pin "2") (pinfunction "2_2") (pintype "passive"))
      (node (ref "C2") (pin "2") (pinfunction "2_2") (pintype "passive"))
      (node (ref "C3") (pin "2") (pinfunction "2_2") (pintype "passive"))
      (node (ref "C4") (pin "2") (pinfunction "2_2") (pintype "passive"))
      (node (ref "C6") (pin "1") (pinfunction "+_1") (pintype "bidirectional"))
      (node (ref "C7") (pin "2") (pinfunction "2_2") (pintype "passive"))
      (node (ref "C8") (pin "2") (pinfunction "2_2") (pintype "passive"))
      (node (ref "C9") (pin "2") (pinfunction "2_2") (pintype "passive"))
      (node (ref "HM1") (pin "2") (pinfunction "CSB_2") (pintype "input"))
      (node (ref "HM1") (pin "5") (pinfunction "SDO_5") (pintype "bidirectional"))
      (node (ref "HM1") (pin "6") (pinfunction "VDDIO_6") (pintype "power_in"))
      (node (ref "HM1") (pin "8") (pinfunction "VDD_8") (pintype "power_in"))
      (node (ref "IC1") (pin "EN") (pinfunction "EN_EN") (pintype "bidirectional"))
      (node (ref "IC1") (pin "VCC") (pinfunction "VCC_VCC") (pintype "power_in"))
      (node (ref "IC12") (pin "18") (pinfunction "VCC_18") (pintype "bidirectional"))
      (node (ref "IC2") (pin "4") (pinfunction "FEEDBACK_4") (pintype "bidirectional"))
      (node (ref "IC3") (pin "1") (pinfunction "VCC_1") (pintype "bidirectional"))
      (node (ref "L1") (pin "2") (pinfunction "2_2") (pintype "bidirectional"))
      (node (ref "NEOPIXEL1") (pin "1") (pinfunction "VDD_1") (pintype "bidirectional"))
      (node (ref "NEOPIXEL10") (pin "1") (pinfunction "VDD_1") (pintype "bidirectional"))
      (node (ref "NEOPIXEL11") (pin "1") (pinfunction "VDD_1") (pintype "bidirectional"))
      (node (ref "NEOPIXEL12") (pin "1") (pinfunction "VDD_1") (pintype "bidirectional"))
      (node (ref "NEOPIXEL13") (pin "1") (pinfunction "VDD_1") (pintype "bidirectional"))
      (node (ref "NEOPIXEL14") (pin "1") (pinfunction "VDD_1") (pintype "bidirectional"))
      (node (ref "NEOPIXEL15") (pin "1") (pinfunction "VDD_1") (pintype "bidirectional"))
      (node (ref "NEOPIXEL16") (pin "1") (pinfunction "VDD_1") (pintype "bidirectional"))
      (node (ref "NEOPIXEL2") (pin "1") (pinfunction "VDD_1") (pintype "bidirectional"))
      (node (ref "NEOPIXEL3") (pin "1") (pinfunction "VDD_1") (pintype "bidirectional"))
      (node (ref "NEOPIXEL4") (pin "1") (pinfunction "VDD_1") (pintype "bidirectional"))
      (node (ref "NEOPIXEL5") (pin "1") (pinfunction "VDD_1") (pintype "bidirectional"))
      (node (ref "NEOPIXEL6") (pin "1") (pinfunction "VDD_1") (pintype "bidirectional"))
      (node (ref "NEOPIXEL7") (pin "1") (pinfunction "VDD_1") (pintype "bidirectional"))
      (node (ref "NEOPIXEL8") (pin "1") (pinfunction "VDD_1") (pintype "bidirectional"))
      (node (ref "NEOPIXEL9") (pin "1") (pinfunction "VDD_1") (pintype "bidirectional"))
      (node (ref "R2") (pin "1") (pinfunction "1_1") (pintype "passive"))
      (node (ref "R21") (pin "2") (pinfunction "2_2") (pintype "passive"))
      (node (ref "R22") (pin "2") (pinfunction "2_2") (pintype "passive"))
      (node (ref "RN1") (pin "6") (pinfunction "2_6") (pintype "passive"))
      (node (ref "RN1") (pin "7") (pinfunction "2_7") (pintype "passive"))
      (node (ref "RN1") (pin "8") (pinfunction "2_8") (pintype "passive"))
      (node (ref "RN2") (pin "5") (pinfunction "2_5") (pintype "passive"))
      (node (ref "RN2") (pin "6") (pinfunction "2_6") (pintype "passive"))
      (node (ref "RN2") (pin "7") (pinfunction "2_7") (pintype "passive"))
      (node (ref "RN2") (pin "8") (pinfunction "2_8") (pintype "passive"))
      (node (ref "RN3") (pin "5") (pinfunction "2_5") (pintype "passive"))
      (node (ref "RN3") (pin "6") (pinfunction "2_6") (pintype "passive"))
      (node (ref "RN3") (pin "7") (pinfunction "2_7") (pintype "passive"))
      (node (ref "RN3") (pin "8") (pinfunction "2_8") (pintype "passive"))
      (node (ref "U$3") (pin "3V3_1") (pinfunction "3V3_3V3_1") (pintype "bidirectional"))
      (node (ref "U$3") (pin "3V3_2") (pinfunction "3V3_3V3_2") (pintype "bidirectional"))
      (node (ref "X1") (pin "3") (pinfunction "3_3") (pintype "passive"))
    )
    (net (code "51") (name "VDD") (class "Default")
      (node (ref "C5") (pin "1") (pinfunction "+_1") (pintype "bidirectional"))
      (node (ref "IC2") (pin "1") (pinfunction "VIN_1") (pintype "input"))
      (node (ref "JP1") (pin "2") (pinfunction "2_2") (pintype "passive"))
    )
    (net (code "52") (name "unconnected-(IC1-PadADC)") (class "Default")
      (node (ref "IC1") (pin "ADC") (pinfunction "ADC_ADC") (pintype "bidirectional"))
    )
    (net (code "53") (name "unconnected-(IC1-PadCS0)") (class "Default")
      (node (ref "IC1") (pin "CS0") (pinfunction "CS0_CS0") (pintype "bidirectional"))
    )
    (net (code "54") (name "unconnected-(IC1-PadIO9)") (class "Default")
      (node (ref "IC1") (pin "IO9") (pinfunction "IO9_IO9") (pintype "bidirectional"))
    )
    (net (code "55") (name "unconnected-(IC1-PadIO10)") (class "Default")
      (node (ref "IC1") (pin "IO10") (pinfunction "IO10_IO10") (pintype "bidirectional"))
    )
    (net (code "56") (name "unconnected-(IC1-PadIO16)") (class "Default")
      (node (ref "IC1") (pin "IO16") (pinfunction "IO16_IO16") (pintype "bidirectional"))
    )
    (net (code "57") (name "unconnected-(IC1-PadMISO)") (class "Default")
      (node (ref "IC1") (pin "MISO") (pinfunction "MISO_MISO") (pintype "bidirectional"))
    )
    (net (code "58") (name "unconnected-(IC1-PadMOSI)") (class "Default")
      (node (ref "IC1") (pin "MOSI") (pinfunction "MOSI_MOSI") (pintype "bidirectional"))
    )
    (net (code "59") (name "unconnected-(IC1-PadSCLK)") (class "Default")
      (node (ref "IC1") (pin "SCLK") (pinfunction "SCLK_SCLK") (pintype "bidirectional"))
    )
    (net (code "60") (name "unconnected-(IC12-NC-Pad7)") (class "Default")
      (node (ref "IC12") (pin "7") (pinfunction "NC_7") (pintype "no_connect"))
    )
    (net (code "61") (name "unconnected-(NEOPIXEL16-DOUT-Pad2)") (class "Default")
      (node (ref "NEOPIXEL16") (pin "2") (pinfunction "DOUT_2") (pintype "bidirectional"))
    )
    (net (code "62") (name "unconnected-(RN2B-1-Pad2)") (class "Default")
      (node (ref "RN2") (pin "2") (pinfunction "1_2") (pintype "passive"))
    )
    (net (code "63") (name "unconnected-(U$3-PadINT)") (class "Default")
      (node (ref "U$3") (pin "INT") (pinfunction "INT_INT") (pintype "bidirectional"))
    )
    (net (code "64") (name "unconnected-(U$3-PadNC)") (class "Default")
      (node (ref "U$3") (pin "NC") (pinfunction "NC_NC") (pintype "no_connect"))
    )
  )
)
